# INA169.net
KiCad netlist of a schematic drawn in Altium Designer
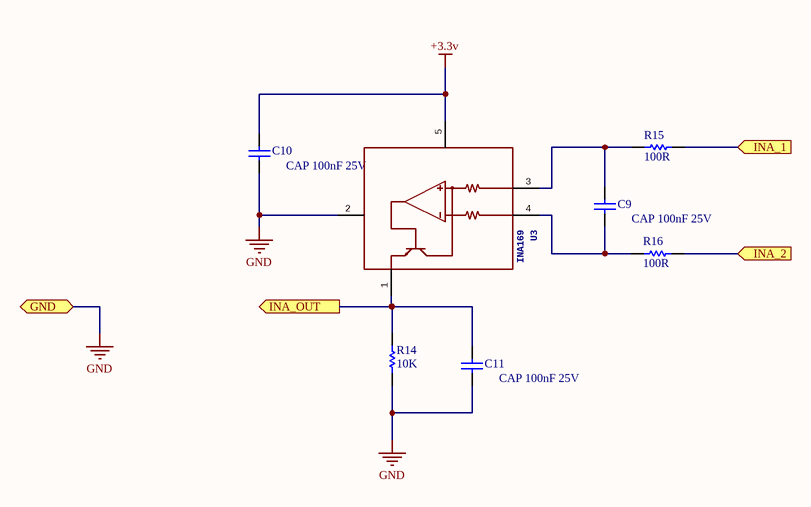
[diagram p0: INA169.SchDoc]

(export (version "E")
  (design (tool "Eeschema 10.0.6"))
  (components
    (comp (ref "C9")
      (value "CAP 100nF 25V")
      (footprint "CAPC0402(1005)60_L")
      (description "CAP 100nF 25V ±20% 0402 (1005 Metric) Thickness 0.6mm SMD")
      (fields (field (name "TOLERANCE") "Â±20%"))
      (libsource (lib "Altium Content Vault") (part "CAP"))
    )
    (comp (ref "C10")
      (value "CAP 100nF 25V")
      (footprint "CAPC0402(1005)60_L")
      (description "CAP 100nF 25V ±20% 0402 (1005 Metric) Thickness 0.6mm SMD")
      (fields (field (name "TOLERANCE") "Â±20%"))
      (libsource (lib "Altium Content Vault") (part "CAP"))
    )
    (comp (ref "C11")
      (value "CAP 100nF 25V")
      (footprint "CAPC0402(1005)60_L")
      (description "CAP 100nF 25V ±20% 0402 (1005 Metric) Thickness 0.6mm SMD")
      (fields (field (name "TOLERANCE") "Â±20%"))
      (libsource (lib "Altium Content Vault") (part "CAP"))
    )
    (comp (ref "R14")
      (value "10K")
      (footprint "RES-0402")
      (description "RES SMD 10K OHM 5% 1/16W 0402")
      (fields (field (name "Comment") "RC0402JR-071KL"))
      (libsource (lib "Schlib1") (part "RES 1K 0402"))
    )
    (comp (ref "R15")
      (value "100R")
      (footprint "RES-0402")
      (description "RES SMD 100 OHM 5% 1/16W 0402")
      (fields (field (name "Comment") "RC0402JR-071KL"))
      (libsource (lib "Schlib1") (part "RES 1K 0402"))
    )
    (comp (ref "R16")
      (value "100R")
      (footprint "RES-0402")
      (description "RES SMD 100 OHM 5% 1/16W 0402")
      (fields (field (name "Comment") "RC0402JR-071KL"))
      (libsource (lib "Schlib1") (part "RES 1K 0402"))
    )
    (comp (ref "U3")
      (value "INA169")
      (footprint "SOT23-5")
      (fields (field (name "MF") "Texas Instruments"))
      (libsource (lib "INA169") (part "INA169"))
    )
  )
  (nets
    (net (code "1") (name "+3.3v") (class "Default")
      (node (ref "C10") (pin "2") (pinfunction "2_2") (pintype "passive"))
      (node (ref "U3") (pin "5") (pinfunction "V+_5") (pintype "passive"))
    )
    (net (code "2") (name "/INA_1") (class "Default")
      (node (ref "R15") (pin "2") (pinfunction "2_2") (pintype "passive"))
    )
    (net (code "3") (name "/INA_2") (class "Default")
      (node (ref "R16") (pin "2") (pinfunction "2_2") (pintype "passive"))
    )
    (net (code "4") (name "/INA_OUT") (class "Default")
      (node (ref "C11") (pin "2") (pinfunction "2_2") (pintype "passive"))
      (node (ref "R14") (pin "2") (pinfunction "2_2") (pintype "passive"))
      (node (ref "U3") (pin "1") (pinfunction "OUT_1") (pintype "passive"))
    )
    (net (code "5") (name "GND") (class "Default")
      (node (ref "C10") (pin "1") (pinfunction "1_1") (pintype "passive"))
      (node (ref "C11") (pin "1") (pinfunction "1_1") (pintype "passive"))
      (node (ref "R14") (pin "1") (pinfunction "1_1") (pintype "passive"))
      (node (ref "U3") (pin "2") (pinfunction "GND_2") (pintype "passive"))
    )
    (net (code "6") (name "Net-(U3-VIN+)") (class "Default")
      (node (ref "C9") (pin "2") (pinfunction "2_2") (pintype "passive"))
      (node (ref "R15") (pin "1") (pinfunction "1_1") (pintype "passive"))
      (node (ref "U3") (pin "3") (pinfunction "VIN+_3") (pintype "passive"))
    )
    (net (code "7") (name "Net-(U3-VIN-)") (class "Default")
      (node (ref "C9") (pin "1") (pinfunction "1_1") (pintype "passive"))
      (node (ref "R16") (pin "1") (pinfunction "1_1") (pintype "passive"))
      (node (ref "U3") (pin "4") (pinfunction "VIN-_4") (pintype "passive"))
    )
  )
)
